# ScrollWheel.net
KiCad netlist of a schematic drawn in Altium Designer
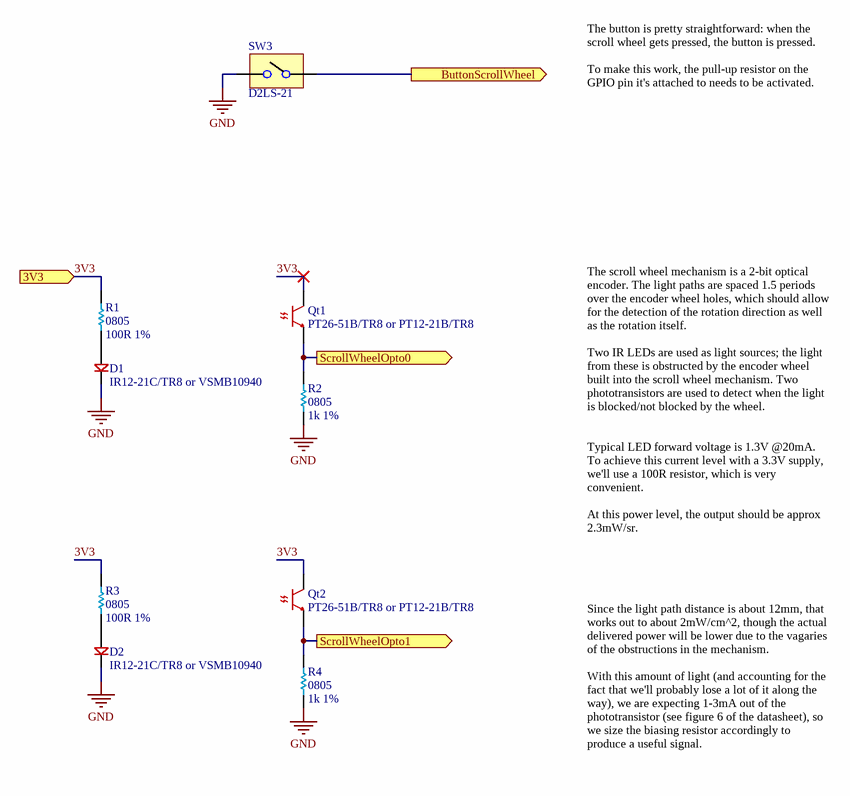
[diagram p0: ScrollWheel.SchDoc]

(export (version "E")
  (design (tool "Eeschema 10.0.6"))
  (components
    (comp (ref "D1")
      (value "IR12-21C/TR8 or VSMB10940")
      (footprint "IR12-21C/TR8")
      (description "Infrared (IR) Emitter 880nm 1.3V 50mA 1mW/sr @ 20mA 30° 2-SMD, No Lead")
      (libsource (lib "LEDs") (part "IR12-21C/TR8"))
    )
    (comp (ref "D2")
      (value "IR12-21C/TR8 or VSMB10940")
      (footprint "IR12-21C/TR8")
      (description "Infrared (IR) Emitter 880nm 1.3V 50mA 1mW/sr @ 20mA 30° 2-SMD, No Lead")
      (libsource (lib "LEDs") (part "IR12-21C/TR8"))
    )
    (comp (ref "Qt1")
      (value "PT26-51B/TR8 or PT12-21B/TR8")
      (footprint "PT26-51B/TR8")
      (description "Phototransistor 940nm Side View 1206 (3216 Metric)")
      (libsource (lib "OptoElectronics") (part "PT26-51B/TR8"))
    )
    (comp (ref "Qt2")
      (value "PT26-51B/TR8 or PT12-21B/TR8")
      (footprint "PT26-51B/TR8")
      (description "Phototransistor 940nm Side View 1206 (3216 Metric)")
      (libsource (lib "OptoElectronics") (part "PT26-51B/TR8"))
    )
    (comp (ref "R1")
      (value "0805")
      (footprint "0805")
      (description "Chip resistor")
      (fields (field (name "ALTIUM_VALUE") "100R 1%"))
      (libsource (lib "Chip_Passives") (part "Res 100R 1% 0805"))
    )
    (comp (ref "R2")
      (value "0805")
      (footprint "0805")
      (description "Chip resistor, 1/8W 100PPM")
      (fields (field (name "ALTIUM_VALUE") "1k 1%"))
      (libsource (lib "Chip_Passives") (part "Res 1k 1% 0805"))
    )
    (comp (ref "R3")
      (value "0805")
      (footprint "0805")
      (description "Chip resistor")
      (fields (field (name "ALTIUM_VALUE") "100R 1%"))
      (libsource (lib "Chip_Passives") (part "Res 100R 1% 0805"))
    )
    (comp (ref "R4")
      (value "0805")
      (footprint "0805")
      (description "Chip resistor, 1/8W 100PPM")
      (fields (field (name "ALTIUM_VALUE") "1k 1%"))
      (libsource (lib "Chip_Passives") (part "Res 1k 1% 0805"))
    )
    (comp (ref "SW3")
      (value "D2LS-21")
      (footprint "D2LS-21")
      (description "Compact Surface-mounting Switch for long durability")
      (libsource (lib "Switches") (part "D2LS-21"))
    )
  )
  (nets
    (net (code "1") (name "/3V3") (class "Default")
      (node (ref "Qt1") (pin "C") (pinfunction "C_C") (pintype "open_collector"))
      (node (ref "Qt2") (pin "C") (pinfunction "C_C") (pintype "open_collector"))
      (node (ref "R1") (pin "2") (pinfunction "2_2") (pintype "passive"))
      (node (ref "R3") (pin "2") (pinfunction "2_2") (pintype "passive"))
    )
    (net (code "2") (name "/ButtonScrollWheel") (class "Default")
      (node (ref "SW3") (pin "A") (pinfunction "A_A") (pintype "passive"))
    )
    (net (code "3") (name "/ScrollWheelOpto0") (class "Default")
      (node (ref "Qt1") (pin "E") (pinfunction "E_E") (pintype "open_emitter"))
      (node (ref "R2") (pin "2") (pinfunction "2_2") (pintype "passive"))
    )
    (net (code "4") (name "/ScrollWheelOpto1") (class "Default")
      (node (ref "Qt2") (pin "E") (pinfunction "E_E") (pintype "open_emitter"))
      (node (ref "R4") (pin "2") (pinfunction "2_2") (pintype "passive"))
    )
    (net (code "5") (name "GND") (class "Default")
      (node (ref "D1") (pin "C") (pinfunction "C_C") (pintype "passive"))
      (node (ref "D2") (pin "C") (pinfunction "C_C") (pintype "passive"))
      (node (ref "R2") (pin "1") (pinfunction "1_1") (pintype "passive"))
      (node (ref "R4") (pin "1") (pinfunction "1_1") (pintype "passive"))
      (node (ref "SW3") (pin "B") (pinfunction "B_B") (pintype "passive"))
    )
    (net (code "6") (name "Net-(D1-PadA)") (class "Default")
      (node (ref "D1") (pin "A") (pinfunction "A_A") (pintype "passive"))
      (node (ref "R1") (pin "1") (pinfunction "1_1") (pintype "passive"))
    )
    (net (code "7") (name "Net-(D2-PadA)") (class "Default")
      (node (ref "D2") (pin "A") (pinfunction "A_A") (pintype "passive"))
      (node (ref "R3") (pin "1") (pinfunction "1_1") (pintype "passive"))
    )
  )
)
